# main.net
KiCad netlist of a schematic drawn in EAGLE
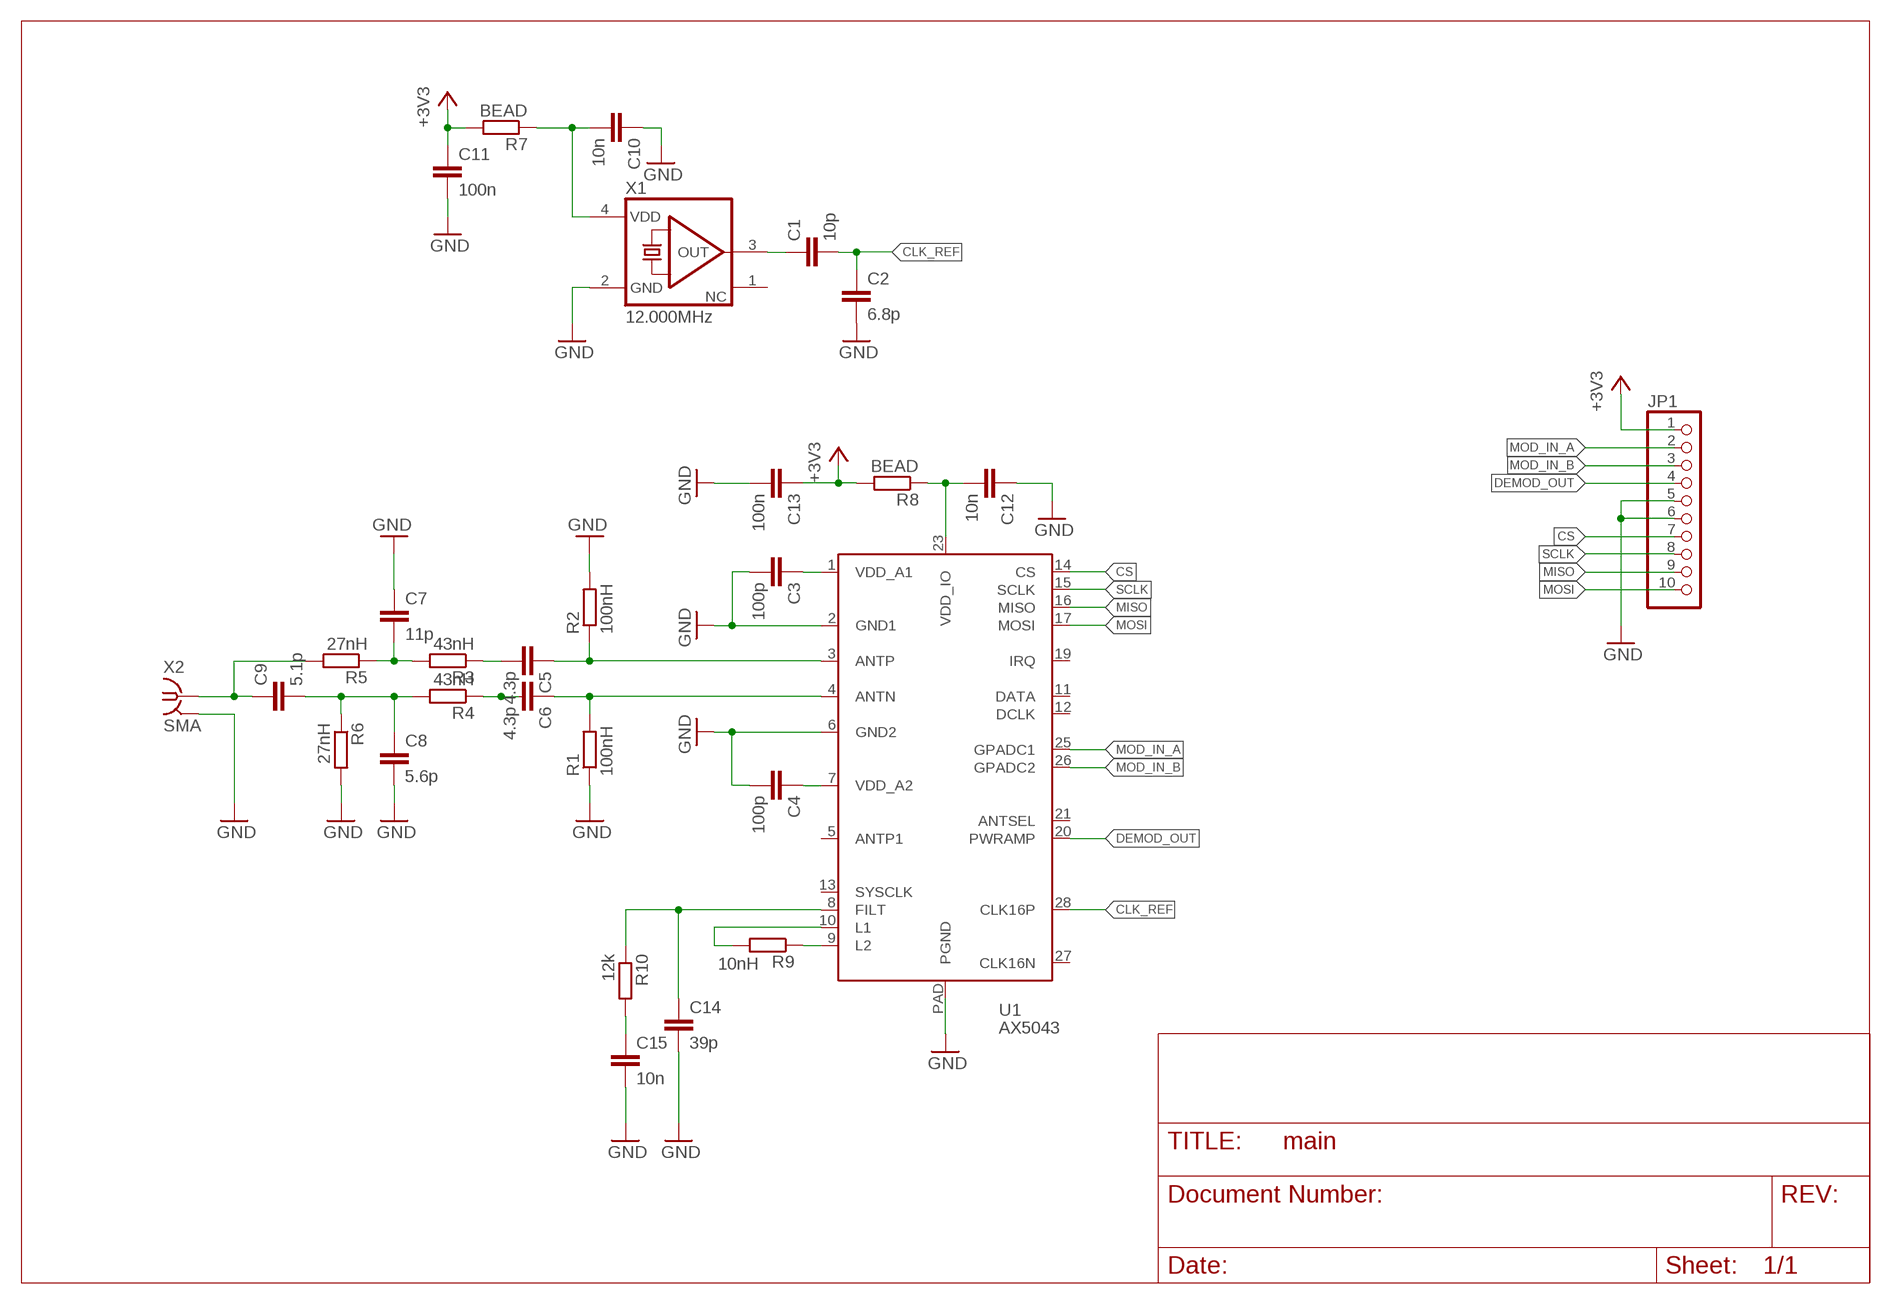
[diagram p0: schematic, sheet 1]

(export (version "E")
  (design (tool "Eeschema 10.0.6"))
  (components
    (comp (ref "C1")
      (value "10p")
      (footprint "eagle-import:C0603")
      (libsource (lib "eagle-import") (part "C-EUC0603"))
    )
    (comp (ref "C2")
      (value "6.8p")
      (footprint "eagle-import:C0603")
      (libsource (lib "eagle-import") (part "C-EUC0603"))
    )
    (comp (ref "C3")
      (value "100p")
      (footprint "eagle-import:C0603")
      (libsource (lib "eagle-import") (part "C-EUC0603"))
    )
    (comp (ref "C4")
      (value "100p")
      (footprint "eagle-import:C0603")
      (libsource (lib "eagle-import") (part "C-EUC0603"))
    )
    (comp (ref "C5")
      (value "4.3p")
      (footprint "eagle-import:C0603")
      (libsource (lib "eagle-import") (part "C-EUC0603"))
    )
    (comp (ref "C6")
      (value "4.3p")
      (footprint "eagle-import:C0603")
      (libsource (lib "eagle-import") (part "C-EUC0603"))
    )
    (comp (ref "C7")
      (value "11p")
      (footprint "eagle-import:C0603")
      (libsource (lib "eagle-import") (part "C-EUC0603"))
    )
    (comp (ref "C8")
      (value "5.6p")
      (footprint "eagle-import:C0603")
      (libsource (lib "eagle-import") (part "C-EUC0603"))
    )
    (comp (ref "C9")
      (value "5.1p")
      (footprint "eagle-import:C0603")
      (libsource (lib "eagle-import") (part "C-EUC0603"))
    )
    (comp (ref "C10")
      (value "10n")
      (footprint "eagle-import:C0603")
      (libsource (lib "eagle-import") (part "C-EUC0603"))
    )
    (comp (ref "C11")
      (value "100n")
      (footprint "eagle-import:C0603")
      (libsource (lib "eagle-import") (part "C-EUC0603"))
    )
    (comp (ref "C12")
      (value "10n")
      (footprint "eagle-import:C0603")
      (libsource (lib "eagle-import") (part "C-EUC0603"))
    )
    (comp (ref "C13")
      (value "100n")
      (footprint "eagle-import:C0603")
      (libsource (lib "eagle-import") (part "C-EUC0603"))
    )
    (comp (ref "C14")
      (value "39p")
      (footprint "eagle-import:C0603")
      (libsource (lib "eagle-import") (part "C-EUC0603"))
    )
    (comp (ref "C15")
      (value "10n")
      (footprint "eagle-import:C0603")
      (libsource (lib "eagle-import") (part "C-EUC0603"))
    )
    (comp (ref "JP1")
      (value "PINHD-1X10")
      (footprint "eagle-import:1X10")
      (libsource (lib "eagle-import") (part "PINHD-1X10"))
    )
    (comp (ref "R1")
      (value "100nH")
      (footprint "eagle-import:R0603")
      (libsource (lib "eagle-import") (part "R-EU_R0603"))
    )
    (comp (ref "R2")
      (value "100nH")
      (footprint "eagle-import:R0603")
      (libsource (lib "eagle-import") (part "R-EU_R0603"))
    )
    (comp (ref "R3")
      (value "43nH")
      (footprint "eagle-import:R0603")
      (libsource (lib "eagle-import") (part "R-EU_R0603"))
    )
    (comp (ref "R4")
      (value "43nH")
      (footprint "eagle-import:R0603")
      (libsource (lib "eagle-import") (part "R-EU_R0603"))
    )
    (comp (ref "R5")
      (value "27nH")
      (footprint "eagle-import:R0603")
      (libsource (lib "eagle-import") (part "R-EU_R0603"))
    )
    (comp (ref "R6")
      (value "27nH")
      (footprint "eagle-import:R0603")
      (libsource (lib "eagle-import") (part "R-EU_R0603"))
    )
    (comp (ref "R7")
      (value "BEAD")
      (footprint "eagle-import:R0603")
      (libsource (lib "eagle-import") (part "R-EU_R0603"))
    )
    (comp (ref "R8")
      (value "BEAD")
      (footprint "eagle-import:R0603")
      (libsource (lib "eagle-import") (part "R-EU_R0603"))
    )
    (comp (ref "R9")
      (value "10nH")
      (footprint "eagle-import:R0603")
      (libsource (lib "eagle-import") (part "R-EU_R0603"))
    )
    (comp (ref "R10")
      (value "12k")
      (footprint "eagle-import:R0603")
      (libsource (lib "eagle-import") (part "R-EU_R0603"))
    )
    (comp (ref "U1")
      (value "AX5043")
      (footprint "eagle-import:QFN28-5X5-WITH-CENTER-PAD")
      (libsource (lib "eagle-import") (part "U-ONSEMI-AX5043"))
    )
    (comp (ref "X1")
      (value "12.000MHz")
      (footprint "eagle-import:ASE")
      (libsource (lib "eagle-import") (part "ASE"))
    )
    (comp (ref "X2")
      (value "SMA")
      (footprint "eagle-import:J502-ND-142-0711-821_826")
      (fields (field (name "MF") "JOHNSON COMPONENTS") (field (name "MPN") "142-0711-821"))
      (libsource (lib "eagle-import") (part "SMA-142-0711-821/826"))
    )
  )
  (nets
    (net (code "1") (name "+3V3") (class "Default")
      (node (ref "C11") (pin "1") (pinfunction "1_1") (pintype "passive"))
      (node (ref "C13") (pin "1") (pinfunction "1_1") (pintype "passive"))
      (node (ref "JP1") (pin "1") (pinfunction "1_1") (pintype "passive"))
      (node (ref "R7") (pin "2") (pinfunction "2_2") (pintype "passive"))
      (node (ref "R8") (pin "2") (pinfunction "2_2") (pintype "passive"))
    )
    (net (code "2") (name "CLK_REF") (class "Default")
      (node (ref "C1") (pin "2") (pinfunction "2_2") (pintype "passive"))
      (node (ref "C2") (pin "1") (pinfunction "1_1") (pintype "passive"))
      (node (ref "U1") (pin "28") (pinfunction "CLK16P_28") (pintype "passive"))
    )
    (net (code "3") (name "CS") (class "Default")
      (node (ref "JP1") (pin "7") (pinfunction "7_7") (pintype "passive"))
      (node (ref "U1") (pin "14") (pinfunction "CS_14") (pintype "input"))
    )
    (net (code "4") (name "DEMOD_OUT") (class "Default")
      (node (ref "JP1") (pin "4") (pinfunction "4_4") (pintype "passive"))
      (node (ref "U1") (pin "20") (pinfunction "PWRAMP_20") (pintype "bidirectional"))
    )
    (net (code "5") (name "GND") (class "Default")
      (node (ref "C10") (pin "1") (pinfunction "1_1") (pintype "passive"))
      (node (ref "C11") (pin "2") (pinfunction "2_2") (pintype "passive"))
      (node (ref "C12") (pin "1") (pinfunction "1_1") (pintype "passive"))
      (node (ref "C13") (pin "2") (pinfunction "2_2") (pintype "passive"))
      (node (ref "C14") (pin "2") (pinfunction "2_2") (pintype "passive"))
      (node (ref "C15") (pin "2") (pinfunction "2_2") (pintype "passive"))
      (node (ref "C2") (pin "2") (pinfunction "2_2") (pintype "passive"))
      (node (ref "C3") (pin "2") (pinfunction "2_2") (pintype "passive"))
      (node (ref "C4") (pin "2") (pinfunction "2_2") (pintype "passive"))
      (node (ref "C7") (pin "1") (pinfunction "1_1") (pintype "passive"))
      (node (ref "C8") (pin "2") (pinfunction "2_2") (pintype "passive"))
      (node (ref "JP1") (pin "5") (pinfunction "5_5") (pintype "passive"))
      (node (ref "JP1") (pin "6") (pinfunction "6_6") (pintype "passive"))
      (node (ref "R1") (pin "1") (pinfunction "1_1") (pintype "passive"))
      (node (ref "R2") (pin "2") (pinfunction "2_2") (pintype "passive"))
      (node (ref "R6") (pin "2") (pinfunction "2_2") (pintype "passive"))
      (node (ref "U1") (pin "2") (pinfunction "GND1_2") (pintype "power_in"))
      (node (ref "U1") (pin "6") (pinfunction "GND2_6") (pintype "power_in"))
      (node (ref "U1") (pin "PAD") (pinfunction "PGND_PAD") (pintype "power_in"))
      (node (ref "X1") (pin "2") (pinfunction "GND_2") (pintype "power_in"))
      (node (ref "X2") (pin "G@1") (pinfunction "2_G@1") (pintype "passive"))
      (node (ref "X2") (pin "G@2") (pinfunction "2_G@2") (pintype "passive"))
      (node (ref "X2") (pin "G@3") (pinfunction "2_G@3") (pintype "passive"))
      (node (ref "X2") (pin "G@4") (pinfunction "2_G@4") (pintype "passive"))
    )
    (net (code "6") (name "MISO") (class "Default")
      (node (ref "JP1") (pin "9") (pinfunction "9_9") (pintype "passive"))
      (node (ref "U1") (pin "16") (pinfunction "MISO_16") (pintype "output"))
    )
    (net (code "7") (name "MOD_IN_A") (class "Default")
      (node (ref "JP1") (pin "2") (pinfunction "2_2") (pintype "passive"))
      (node (ref "U1") (pin "25") (pinfunction "GPADC1_25") (pintype "input"))
    )
    (net (code "8") (name "MOD_IN_B") (class "Default")
      (node (ref "JP1") (pin "3") (pinfunction "3_3") (pintype "passive"))
      (node (ref "U1") (pin "26") (pinfunction "GPADC2_26") (pintype "input"))
    )
    (net (code "9") (name "MOSI") (class "Default")
      (node (ref "JP1") (pin "10") (pinfunction "10_10") (pintype "passive"))
      (node (ref "U1") (pin "17") (pinfunction "MOSI_17") (pintype "input"))
    )
    (net (code "10") (name "Net-(C5-Pad2)") (class "Default")
      (node (ref "C5") (pin "2") (pinfunction "2_2") (pintype "passive"))
      (node (ref "R3") (pin "1") (pinfunction "1_1") (pintype "passive"))
    )
    (net (code "11") (name "Net-(C6-Pad2)") (class "Default")
      (node (ref "C6") (pin "2") (pinfunction "2_2") (pintype "passive"))
      (node (ref "R4") (pin "1") (pinfunction "1_1") (pintype "passive"))
    )
    (net (code "12") (name "Net-(C7-Pad2)") (class "Default")
      (node (ref "C7") (pin "2") (pinfunction "2_2") (pintype "passive"))
      (node (ref "R3") (pin "2") (pinfunction "2_2") (pintype "passive"))
      (node (ref "R5") (pin "1") (pinfunction "1_1") (pintype "passive"))
    )
    (net (code "13") (name "Net-(C8-Pad1)") (class "Default")
      (node (ref "C8") (pin "1") (pinfunction "1_1") (pintype "passive"))
      (node (ref "C9") (pin "2") (pinfunction "2_2") (pintype "passive"))
      (node (ref "R4") (pin "2") (pinfunction "2_2") (pintype "passive"))
      (node (ref "R6") (pin "1") (pinfunction "1_1") (pintype "passive"))
    )
    (net (code "14") (name "Net-(C9-Pad1)") (class "Default")
      (node (ref "C9") (pin "1") (pinfunction "1_1") (pintype "passive"))
      (node (ref "R5") (pin "2") (pinfunction "2_2") (pintype "passive"))
      (node (ref "X2") (pin "1") (pinfunction "1_1") (pintype "passive"))
    )
    (net (code "15") (name "Net-(C15-Pad1)") (class "Default")
      (node (ref "C15") (pin "1") (pinfunction "1_1") (pintype "passive"))
      (node (ref "R10") (pin "2") (pinfunction "2_2") (pintype "passive"))
    )
    (net (code "16") (name "Net-(U1-ANTN)") (class "Default")
      (node (ref "C6") (pin "1") (pinfunction "1_1") (pintype "passive"))
      (node (ref "R1") (pin "2") (pinfunction "2_2") (pintype "passive"))
      (node (ref "U1") (pin "4") (pinfunction "ANTN_4") (pintype "bidirectional"))
    )
    (net (code "17") (name "Net-(U1-ANTP)") (class "Default")
      (node (ref "C5") (pin "1") (pinfunction "1_1") (pintype "passive"))
      (node (ref "R2") (pin "1") (pinfunction "1_1") (pintype "passive"))
      (node (ref "U1") (pin "3") (pinfunction "ANTP_3") (pintype "bidirectional"))
    )
    (net (code "18") (name "Net-(U1-FILT)") (class "Default")
      (node (ref "C14") (pin "1") (pinfunction "1_1") (pintype "passive"))
      (node (ref "R10") (pin "1") (pinfunction "1_1") (pintype "passive"))
      (node (ref "U1") (pin "8") (pinfunction "FILT_8") (pintype "output"))
    )
    (net (code "19") (name "Net-(U1-L1)") (class "Default")
      (node (ref "R9") (pin "2") (pinfunction "2_2") (pintype "passive"))
      (node (ref "U1") (pin "10") (pinfunction "L1_10") (pintype "bidirectional"))
    )
    (net (code "20") (name "Net-(U1-L2)") (class "Default")
      (node (ref "R9") (pin "1") (pinfunction "1_1") (pintype "passive"))
      (node (ref "U1") (pin "9") (pinfunction "L2_9") (pintype "bidirectional"))
    )
    (net (code "21") (name "Net-(U1-VDD_A1)") (class "Default")
      (node (ref "C3") (pin "1") (pinfunction "1_1") (pintype "passive"))
      (node (ref "U1") (pin "1") (pinfunction "VDD_A1_1") (pintype "power_in"))
    )
    (net (code "22") (name "Net-(U1-VDD_A2)") (class "Default")
      (node (ref "C4") (pin "1") (pinfunction "1_1") (pintype "passive"))
      (node (ref "U1") (pin "7") (pinfunction "VDD_A2_7") (pintype "power_in"))
    )
    (net (code "23") (name "Net-(U1-VDD_IO)") (class "Default")
      (node (ref "C12") (pin "2") (pinfunction "2_2") (pintype "passive"))
      (node (ref "R8") (pin "1") (pinfunction "1_1") (pintype "passive"))
      (node (ref "U1") (pin "23") (pinfunction "VDD_IO_23") (pintype "power_in"))
    )
    (net (code "24") (name "Net-(X1-OUT)") (class "Default")
      (node (ref "C1") (pin "1") (pinfunction "1_1") (pintype "passive"))
      (node (ref "X1") (pin "3") (pinfunction "OUT_3") (pintype "output"))
    )
    (net (code "25") (name "Net-(X1-VDD)") (class "Default")
      (node (ref "C10") (pin "2") (pinfunction "2_2") (pintype "passive"))
      (node (ref "R7") (pin "1") (pinfunction "1_1") (pintype "passive"))
      (node (ref "X1") (pin "4") (pinfunction "VDD_4") (pintype "power_in"))
    )
    (net (code "26") (name "SCLK") (class "Default")
      (node (ref "JP1") (pin "8") (pinfunction "8_8") (pintype "passive"))
      (node (ref "U1") (pin "15") (pinfunction "SCLK_15") (pintype "input"))
    )
    (net (code "27") (name "unconnected-(U1-ANTP1-Pad5)") (class "Default")
      (node (ref "U1") (pin "5") (pinfunction "ANTP1_5") (pintype "bidirectional"))
    )
    (net (code "28") (name "unconnected-(U1-ANTSEL-Pad21)") (class "Default")
      (node (ref "U1") (pin "21") (pinfunction "ANTSEL_21") (pintype "bidirectional"))
    )
    (net (code "29") (name "unconnected-(U1-CLK16N-Pad27)") (class "Default")
      (node (ref "U1") (pin "27") (pinfunction "CLK16N_27") (pintype "passive"))
    )
    (net (code "30") (name "unconnected-(U1-DATA-Pad11)") (class "Default")
      (node (ref "U1") (pin "11") (pinfunction "DATA_11") (pintype "bidirectional"))
    )
    (net (code "31") (name "unconnected-(U1-DCLK-Pad12)") (class "Default")
      (node (ref "U1") (pin "12") (pinfunction "DCLK_12") (pintype "bidirectional"))
    )
    (net (code "32") (name "unconnected-(U1-IRQ-Pad19)") (class "Default")
      (node (ref "U1") (pin "19") (pinfunction "IRQ_19") (pintype "bidirectional"))
    )
    (net (code "33") (name "unconnected-(U1-SYSCLK-Pad13)") (class "Default")
      (node (ref "U1") (pin "13") (pinfunction "SYSCLK_13") (pintype "bidirectional"))
    )
    (net (code "34") (name "unconnected-(X1-NC-Pad1)") (class "Default")
      (node (ref "X1") (pin "1") (pinfunction "NC_1") (pintype "input"))
    )
  )
)
